# OfficeSign.net
KiCad netlist of a schematic drawn in EAGLE
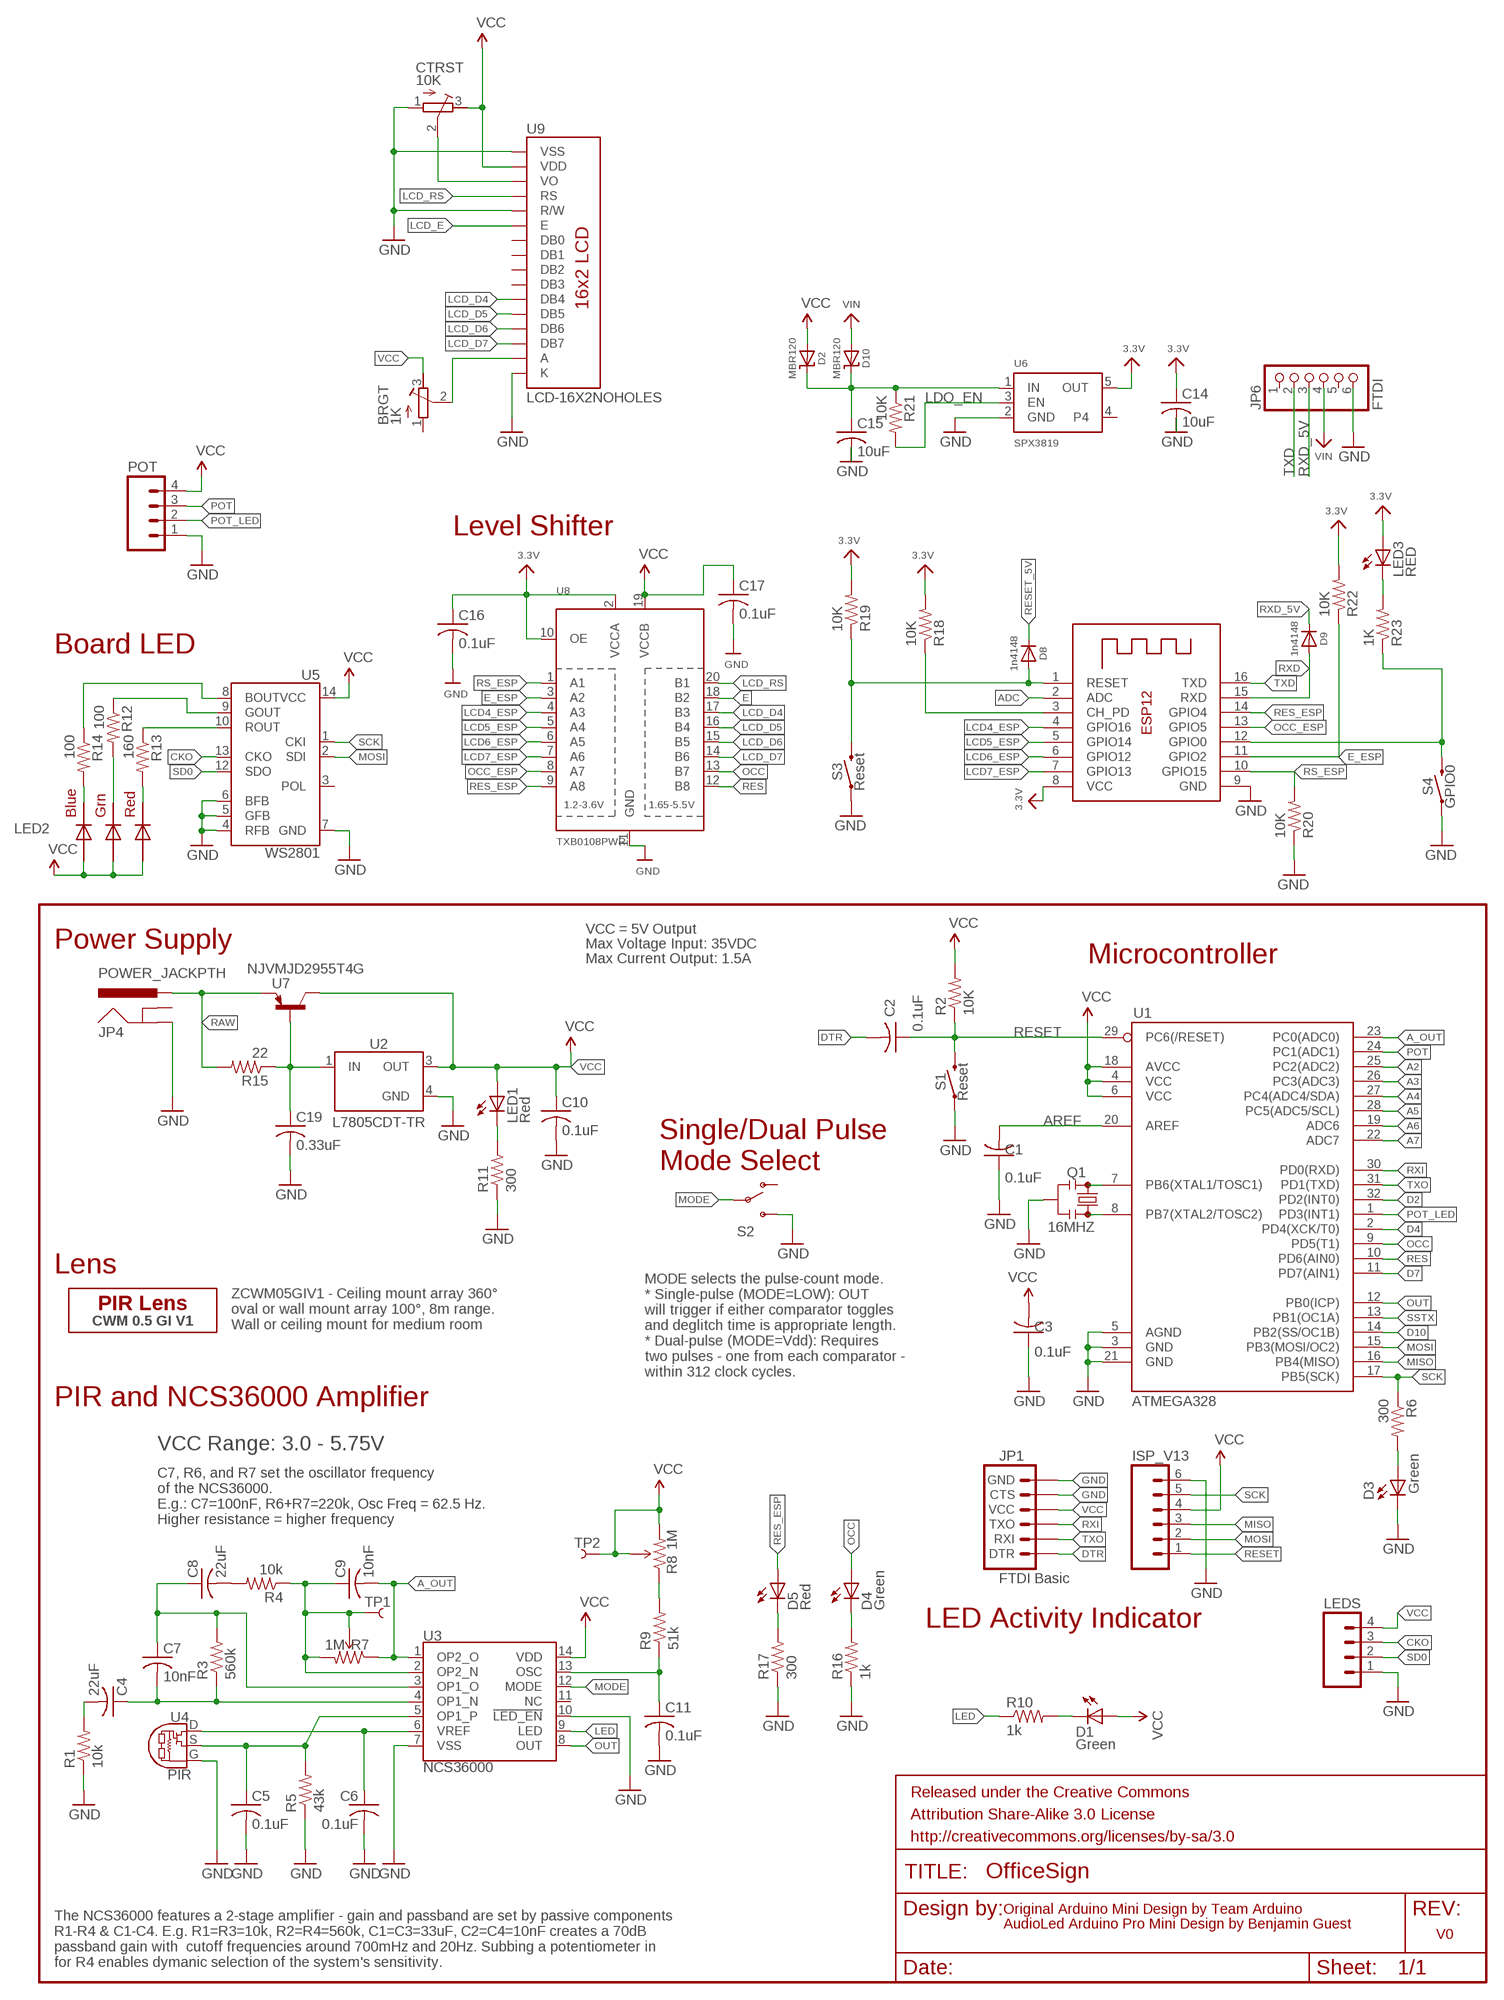
[diagram p0: schematic, sheet 1]

(export (version "E")
  (design (tool "Eeschema 10.0.6"))
  (components
    (comp (ref "BRGT")
      (value "1K")
      (footprint "eagle-import:RTRIM3296W")
      (libsource (lib "eagle-import") (part "R-TRIMM3296W"))
    )
    (comp (ref "C1")
      (value "0.1uF")
      (footprint "eagle-import:C0805")
      (libsource (lib "eagle-import") (part "C-USC0805"))
    )
    (comp (ref "C2")
      (value "0.1uF")
      (footprint "eagle-import:C0805")
      (libsource (lib "eagle-import") (part "C-USC0805"))
    )
    (comp (ref "C3")
      (value "0.1uF")
      (footprint "eagle-import:C0805")
      (libsource (lib "eagle-import") (part "C-USC0805"))
    )
    (comp (ref "C4")
      (value "22uF")
      (footprint "eagle-import:C0805")
      (libsource (lib "eagle-import") (part "C-USC0805"))
    )
    (comp (ref "C5")
      (value "0.1uF")
      (footprint "eagle-import:C0805")
      (libsource (lib "eagle-import") (part "C-USC0805"))
    )
    (comp (ref "C6")
      (value "0.1uF")
      (footprint "eagle-import:C0805")
      (libsource (lib "eagle-import") (part "C-USC0805"))
    )
    (comp (ref "C7")
      (value "10nF")
      (footprint "eagle-import:C0805")
      (libsource (lib "eagle-import") (part "C-USC0805"))
    )
    (comp (ref "C8")
      (value "22uF")
      (footprint "eagle-import:C0805")
      (libsource (lib "eagle-import") (part "C-USC0805"))
    )
    (comp (ref "C9")
      (value "10nF")
      (footprint "eagle-import:C0805")
      (libsource (lib "eagle-import") (part "C-USC0805"))
    )
    (comp (ref "C10")
      (value "0.1uF")
      (footprint "eagle-import:C0805")
      (libsource (lib "eagle-import") (part "C-USC0805"))
    )
    (comp (ref "C11")
      (value "0.1uF")
      (footprint "eagle-import:C0805")
      (libsource (lib "eagle-import") (part "C-USC0805"))
    )
    (comp (ref "C14")
      (value "10uF")
      (footprint "eagle-import:C0805")
      (libsource (lib "eagle-import") (part "C-USC0805"))
    )
    (comp (ref "C15")
      (value "10uF")
      (footprint "eagle-import:C0805")
      (libsource (lib "eagle-import") (part "C-USC0805"))
    )
    (comp (ref "C16")
      (value "0.1uF")
      (footprint "eagle-import:C0805")
      (libsource (lib "eagle-import") (part "rcl_334_C-USC0805"))
    )
    (comp (ref "C17")
      (value "0.1uF")
      (footprint "eagle-import:C0805")
      (libsource (lib "eagle-import") (part "rcl_334_C-USC0805"))
    )
    (comp (ref "C19")
      (value "0.33uF")
      (footprint "eagle-import:C0805")
      (libsource (lib "eagle-import") (part "C-USC0805"))
    )
    (comp (ref "CTRST")
      (value "10K")
      (footprint "eagle-import:RTRIM3296W")
      (libsource (lib "eagle-import") (part "R-TRIMM3296W"))
    )
    (comp (ref "D1")
      (value "Green")
      (footprint "eagle-import:CHIPLED_0805")
      (libsource (lib "eagle-import") (part "LEDCHIPLED_0805"))
    )
    (comp (ref "D2")
      (value "MBR120")
      (footprint "eagle-import:SOD-123")
      (libsource (lib "eagle-import") (part "DIODE-SCHOTTKYSOD-123"))
    )
    (comp (ref "D3")
      (value "Green")
      (footprint "eagle-import:CHIPLED_0805")
      (libsource (lib "eagle-import") (part "LEDCHIPLED_0805"))
    )
    (comp (ref "D4")
      (value "Green")
      (footprint "eagle-import:CHIPLED_0805")
      (libsource (lib "eagle-import") (part "LEDCHIPLED_0805"))
    )
    (comp (ref "D5")
      (value "Red")
      (footprint "eagle-import:CHIPLED_0805")
      (libsource (lib "eagle-import") (part "LEDCHIPLED_0805"))
    )
    (comp (ref "D8")
      (value "1n4148")
      (footprint "eagle-import:SOD-323")
      (libsource (lib "eagle-import") (part "DIODESOD-323"))
    )
    (comp (ref "D9")
      (value "1n4148")
      (footprint "eagle-import:SOD-323")
      (libsource (lib "eagle-import") (part "DIODESOD-323"))
    )
    (comp (ref "D10")
      (value "MBR120")
      (footprint "eagle-import:SOD-123")
      (libsource (lib "eagle-import") (part "DIODE-SCHOTTKYSOD-123"))
    )
    (comp (ref "FRAME1")
      (value "FRAME-LETTER")
      (footprint "eagle-import:CREATIVE_COMMONS")
      (libsource (lib "eagle-import") (part "FRAME-LETTER"))
    )
    (comp (ref "ISP_V13")
      (value "M06SIP")
      (footprint "eagle-import:1X06")
      (libsource (lib "eagle-import") (part "M06SIP"))
    )
    (comp (ref "JP1")
      (value "FTDI Basic")
      (footprint "eagle-import:1X06")
      (libsource (lib "eagle-import") (part "ARDUINO_SERIAL_PROGRAMPTH"))
    )
    (comp (ref "JP4")
      (value "POWER_JACKPTH")
      (footprint "eagle-import:POWER_JACK_PTH")
      (libsource (lib "eagle-import") (part "POWER_JACKPTH"))
    )
    (comp (ref "JP6")
      (value "FTDI")
      (footprint "eagle-import:1X06_ROUND_70")
      (libsource (lib "eagle-import") (part "HEADER-1X670MIL"))
    )
    (comp (ref "LED1")
      (value "Red")
      (footprint "eagle-import:CHIPLED_0805")
      (libsource (lib "eagle-import") (part "LEDCHIPLED_0805"))
    )
    (comp (ref "LED2")
      (value "RGBLED5050")
      (footprint "eagle-import:RGBLED5050")
      (libsource (lib "eagle-import") (part "RGBLED5050"))
    )
    (comp (ref "LED3")
      (value "RED")
      (footprint "eagle-import:CHIP-LED0805")
      (libsource (lib "eagle-import") (part "LEDCHIP-LED0805"))
    )
    (comp (ref "LEDS")
      (value "M04JST-PTH")
      (footprint "eagle-import:JST-4-PTH")
      (libsource (lib "eagle-import") (part "M04JST-PTH"))
    )
    (comp (ref "POT")
      (value "M04JST-PTH")
      (footprint "eagle-import:JST-4-PTH")
      (libsource (lib "eagle-import") (part "M04JST-PTH"))
    )
    (comp (ref "Q1")
      (value "16MHZ")
      (footprint "eagle-import:RESONATOR-SMD")
      (libsource (lib "eagle-import") (part "RESONATOR16MHZ"))
    )
    (comp (ref "R1")
      (value "10k")
      (footprint "eagle-import:M0805")
      (libsource (lib "eagle-import") (part "R-US_M0805"))
    )
    (comp (ref "R2")
      (value "10K")
      (footprint "eagle-import:M0805")
      (libsource (lib "eagle-import") (part "R-US_M0805"))
    )
    (comp (ref "R3")
      (value "560k")
      (footprint "eagle-import:M0805")
      (libsource (lib "eagle-import") (part "R-US_M0805"))
    )
    (comp (ref "R4")
      (value "10k")
      (footprint "eagle-import:M0805")
      (libsource (lib "eagle-import") (part "R-US_M0805"))
    )
    (comp (ref "R5")
      (value "43k")
      (footprint "eagle-import:M0805")
      (libsource (lib "eagle-import") (part "R-US_M0805"))
    )
    (comp (ref "R6")
      (value "300")
      (footprint "eagle-import:M0805")
      (libsource (lib "eagle-import") (part "R-US_M0805"))
    )
    (comp (ref "R7")
      (value "1M")
      (footprint "eagle-import:TRIMPOT-TC33X")
      (libsource (lib "eagle-import") (part "TRIMPOTTX33X-1M"))
    )
    (comp (ref "R8")
      (value "1M")
      (footprint "eagle-import:TRIMPOT-TC33X")
      (libsource (lib "eagle-import") (part "TRIMPOTTX33X-1M"))
    )
    (comp (ref "R9")
      (value "51k")
      (footprint "eagle-import:M0805")
      (libsource (lib "eagle-import") (part "R-US_M0805"))
    )
    (comp (ref "R10")
      (value "1k")
      (footprint "eagle-import:M0805")
      (libsource (lib "eagle-import") (part "R-US_M0805"))
    )
    (comp (ref "R11")
      (value "300")
      (footprint "eagle-import:M0805")
      (libsource (lib "eagle-import") (part "R-US_M0805"))
    )
    (comp (ref "R12")
      (value "100")
      (footprint "eagle-import:M0805")
      (libsource (lib "eagle-import") (part "R-US_M0805"))
    )
    (comp (ref "R13")
      (value "160")
      (footprint "eagle-import:M0805")
      (libsource (lib "eagle-import") (part "R-US_M0805"))
    )
    (comp (ref "R14")
      (value "100")
      (footprint "eagle-import:M0805")
      (libsource (lib "eagle-import") (part "R-US_M0805"))
    )
    (comp (ref "R15")
      (value "22")
      (footprint "eagle-import:M0805")
      (libsource (lib "eagle-import") (part "R-US_M0805"))
    )
    (comp (ref "R16")
      (value "1k")
      (footprint "eagle-import:M0805")
      (libsource (lib "eagle-import") (part "R-US_M0805"))
    )
    (comp (ref "R17")
      (value "300")
      (footprint "eagle-import:M0805")
      (libsource (lib "eagle-import") (part "R-US_M0805"))
    )
    (comp (ref "R18")
      (value "10K")
      (footprint "eagle-import:M0805")
      (libsource (lib "eagle-import") (part "R-US_M0805"))
    )
    (comp (ref "R19")
      (value "10K")
      (footprint "eagle-import:M0805")
      (libsource (lib "eagle-import") (part "R-US_M0805"))
    )
    (comp (ref "R20")
      (value "10K")
      (footprint "eagle-import:M0805")
      (libsource (lib "eagle-import") (part "R-US_M0805"))
    )
    (comp (ref "R21")
      (value "10K")
      (footprint "eagle-import:M0805")
      (libsource (lib "eagle-import") (part "R-US_M0805"))
    )
    (comp (ref "R22")
      (value "10K")
      (footprint "eagle-import:M0805")
      (libsource (lib "eagle-import") (part "R-US_M0805"))
    )
    (comp (ref "R23")
      (value "1K")
      (footprint "eagle-import:M0805")
      (libsource (lib "eagle-import") (part "R-US_M0805"))
    )
    (comp (ref "S1")
      (value "Reset")
      (footprint "eagle-import:TACTILE_SWITCH_SMD_5.2MM")
      (libsource (lib "eagle-import") (part "MOMENTARY-SWITCH-SPST-SMD-5.2-REDUNDANT"))
    )
    (comp (ref "S2")
      (value "SWITCH-SPDT-SMD-A")
      (footprint "eagle-import:SWITCH-SPST-SMD-A")
      (libsource (lib "eagle-import") (part "SWITCH-SPDT-SMD-A"))
    )
    (comp (ref "S3")
      (value "Reset")
      (footprint "eagle-import:TACTILE_SWITCH_SMD_5.2MM")
      (libsource (lib "eagle-import") (part "MOMENTARY-SWITCH-SPST-SMD-5.2-REDUNDANT"))
    )
    (comp (ref "S4")
      (value "GPIO0")
      (footprint "eagle-import:TACTILE_SWITCH_SMD_5.2MM")
      (libsource (lib "eagle-import") (part "MOMENTARY-SWITCH-SPST-SMD-5.2-REDUNDANT"))
    )
    (comp (ref "TP1")
      (value "TEST-POINT3X5")
      (footprint "eagle-import:PAD.03X.05")
      (libsource (lib "eagle-import") (part "TEST-POINT3X5"))
    )
    (comp (ref "TP2")
      (value "TEST-POINT3X5")
      (footprint "eagle-import:PAD.03X.05")
      (libsource (lib "eagle-import") (part "TEST-POINT3X5"))
    )
    (comp (ref "U$1")
      (value "CWM 0.5 GI V1")
      (footprint "eagle-import:LENS-CWM-0.5-GI-V1")
      (libsource (lib "eagle-import") (part "PIR-LENSCWM-0.5-GI-V1"))
    )
    (comp (ref "U1")
      (value "ATMEGA328")
      (footprint "eagle-import:TQFP32-08")
      (libsource (lib "eagle-import") (part "ATMEGA168"))
    )
    (comp (ref "U2")
      (value "L7805CDT-TR")
      (footprint "eagle-import:DPAK")
      (libsource (lib "eagle-import") (part "L7805CDT-TR"))
    )
    (comp (ref "U3")
      (value "NCS36000")
      (footprint "eagle-import:SO14")
      (libsource (lib "eagle-import") (part "NCS36000"))
    )
    (comp (ref "U4")
      (value "PIR")
      (footprint "eagle-import:PIR")
      (libsource (lib "eagle-import") (part "PIR"))
    )
    (comp (ref "U5")
      (value "WS2801")
      (footprint "eagle-import:SOP-14")
      (libsource (lib "eagle-import") (part "WS2801"))
    )
    (comp (ref "U6")
      (value "SPX3819")
      (footprint "eagle-import:SOT23-5")
      (libsource (lib "eagle-import") (part "VREG_SOT23-5"))
    )
    (comp (ref "U7")
      (value "NJVMJD2955T4G")
      (footprint "eagle-import:DPAK")
      (libsource (lib "eagle-import") (part "NJVMJD2955T4G"))
    )
    (comp (ref "U8")
      (value "TXB0108PWR")
      (footprint "eagle-import:TSSOP20")
      (libsource (lib "eagle-import") (part "TXB0108PWR"))
    )
    (comp (ref "U9")
      (value "LCD-16X2NOHOLES")
      (footprint "eagle-import:LCD-16X2_NOHOLES")
      (libsource (lib "eagle-import") (part "LCD-16X2NOHOLES"))
    )
    (comp (ref "X2")
      (value "ESP-12")
      (footprint "eagle-import:ESP-12")
      (libsource (lib "eagle-import") (part "ESP-12"))
    )
  )
  (nets
    (net (code "1") (name "/AREF") (class "Default")
      (node (ref "C1") (pin "2") (pinfunction "2_2") (pintype "passive"))
      (node (ref "U1") (pin "20") (pinfunction "AREF_20") (pintype "bidirectional"))
    )
    (net (code "2") (name "/LDO_EN") (class "Default")
      (node (ref "R21") (pin "2") (pinfunction "2_2") (pintype "passive"))
      (node (ref "U6") (pin "3") (pinfunction "EN_3") (pintype "input"))
    )
    (net (code "3") (name "3.3V") (class "Default")
      (node (ref "C14") (pin "1") (pinfunction "1_1") (pintype "passive"))
      (node (ref "C16") (pin "1") (pinfunction "1_1") (pintype "passive"))
      (node (ref "LED3") (pin "A") (pinfunction "A_A") (pintype "passive"))
      (node (ref "R18") (pin "2") (pinfunction "2_2") (pintype "passive"))
      (node (ref "R19") (pin "2") (pinfunction "2_2") (pintype "passive"))
      (node (ref "R22") (pin "2") (pinfunction "2_2") (pintype "passive"))
      (node (ref "U6") (pin "5") (pinfunction "OUT_5") (pintype "power_in"))
      (node (ref "U8") (pin "10") (pinfunction "OE_10") (pintype "bidirectional"))
      (node (ref "U8") (pin "2") (pinfunction "VCCA_2") (pintype "bidirectional"))
      (node (ref "X2") (pin "8") (pinfunction "VCC_8") (pintype "power_in"))
    )
    (net (code "4") (name "A2") (class "Default")
      (node (ref "U1") (pin "25") (pinfunction "PC2(ADC2)_25") (pintype "bidirectional"))
    )
    (net (code "5") (name "A3") (class "Default")
      (node (ref "U1") (pin "26") (pinfunction "PC3(ADC3)_26") (pintype "bidirectional"))
    )
    (net (code "6") (name "A4") (class "Default")
      (node (ref "U1") (pin "27") (pinfunction "PC4(ADC4/SDA)_27") (pintype "bidirectional"))
    )
    (net (code "7") (name "A5") (class "Default")
      (node (ref "U1") (pin "28") (pinfunction "PC5(ADC5/SCL)_28") (pintype "bidirectional"))
    )
    (net (code "8") (name "A6") (class "Default")
      (node (ref "U1") (pin "19") (pinfunction "ADC6_19") (pintype "bidirectional"))
    )
    (net (code "9") (name "A7") (class "Default")
      (node (ref "U1") (pin "22") (pinfunction "ADC7_22") (pintype "bidirectional"))
    )
    (net (code "10") (name "ADC") (class "Default")
      (node (ref "X2") (pin "2") (pinfunction "ADC_2") (pintype "passive"))
    )
    (net (code "11") (name "A_OUT") (class "Default")
      (node (ref "C9") (pin "2") (pinfunction "2_2") (pintype "passive"))
      (node (ref "R7") (pin "1") (pinfunction "CCW_1") (pintype "passive"))
      (node (ref "U1") (pin "23") (pinfunction "PC0(ADC0)_23") (pintype "bidirectional"))
      (node (ref "U3") (pin "1") (pinfunction "OP2_O_1") (pintype "bidirectional"))
    )
    (net (code "12") (name "CKO") (class "Default")
      (node (ref "LEDS") (pin "3") (pinfunction "3_3") (pintype "passive"))
      (node (ref "U5") (pin "13") (pinfunction "CKO_13") (pintype "bidirectional"))
    )
    (net (code "13") (name "D2") (class "Default")
      (node (ref "U1") (pin "32") (pinfunction "PD2(INT0)_32") (pintype "bidirectional"))
    )
    (net (code "14") (name "D4") (class "Default")
      (node (ref "U1") (pin "2") (pinfunction "PD4(XCK/T0)_2") (pintype "bidirectional"))
    )
    (net (code "15") (name "D7") (class "Default")
      (node (ref "U1") (pin "11") (pinfunction "PD7(AIN1)_11") (pintype "bidirectional"))
    )
    (net (code "16") (name "D10") (class "Default")
      (node (ref "U1") (pin "14") (pinfunction "PB2(SS/OC1B)_14") (pintype "bidirectional"))
    )
    (net (code "17") (name "DTR") (class "Default")
      (node (ref "C2") (pin "2") (pinfunction "2_2") (pintype "passive"))
      (node (ref "JP1") (pin "1") (pinfunction "DTR_1") (pintype "passive"))
    )
    (net (code "18") (name "E") (class "Default")
      (node (ref "U8") (pin "18") (pinfunction "B2_18") (pintype "bidirectional"))
    )
    (net (code "19") (name "E_ESP") (class "Default")
      (node (ref "R22") (pin "1") (pinfunction "1_1") (pintype "passive"))
      (node (ref "U8") (pin "3") (pinfunction "A2_3") (pintype "bidirectional"))
      (node (ref "X2") (pin "11") (pinfunction "GPIO2_11") (pintype "bidirectional"))
    )
    (net (code "20") (name "GND") (class "Default")
      (node (ref "C1") (pin "1") (pinfunction "1_1") (pintype "passive"))
      (node (ref "C10") (pin "2") (pinfunction "2_2") (pintype "passive"))
      (node (ref "C11") (pin "2") (pinfunction "2_2") (pintype "passive"))
      (node (ref "C14") (pin "2") (pinfunction "2_2") (pintype "passive"))
      (node (ref "C15") (pin "2") (pinfunction "2_2") (pintype "passive"))
      (node (ref "C16") (pin "2") (pinfunction "2_2") (pintype "passive"))
      (node (ref "C17") (pin "2") (pinfunction "2_2") (pintype "passive"))
      (node (ref "C19") (pin "2") (pinfunction "2_2") (pintype "passive"))
      (node (ref "C3") (pin "1") (pinfunction "1_1") (pintype "passive"))
      (node (ref "C5") (pin "2") (pinfunction "2_2") (pintype "passive"))
      (node (ref "C6") (pin "2") (pinfunction "2_2") (pintype "passive"))
      (node (ref "CTRST") (pin "1") (pinfunction "A_1") (pintype "passive"))
      (node (ref "D3") (pin "C") (pinfunction "C_C") (pintype "passive"))
      (node (ref "ISP_V13") (pin "6") (pinfunction "6_6") (pintype "passive"))
      (node (ref "JP1") (pin "5") (pinfunction "CTS_5") (pintype "passive"))
      (node (ref "JP1") (pin "6") (pinfunction "GND_6") (pintype "passive"))
      (node (ref "JP4") (pin "GND") (pinfunction "GND_GND") (pintype "bidirectional"))
      (node (ref "JP6") (pin "6") (pinfunction "6_6") (pintype "passive"))
      (node (ref "LEDS") (pin "1") (pinfunction "1_1") (pintype "passive"))
      (node (ref "POT") (pin "1") (pinfunction "1_1") (pintype "passive"))
      (node (ref "Q1") (pin "2") (pinfunction "2_2") (pintype "passive"))
      (node (ref "R1") (pin "1") (pinfunction "1_1") (pintype "passive"))
      (node (ref "R11") (pin "1") (pinfunction "1_1") (pintype "passive"))
      (node (ref "R16") (pin "1") (pinfunction "1_1") (pintype "passive"))
      (node (ref "R17") (pin "1") (pinfunction "1_1") (pintype "passive"))
      (node (ref "R20") (pin "1") (pinfunction "1_1") (pintype "passive"))
      (node (ref "R5") (pin "1") (pinfunction "1_1") (pintype "passive"))
      (node (ref "S1") (pin "1") (pinfunction "1_1") (pintype "passive"))
      (node (ref "S1") (pin "2") (pinfunction "1_2") (pintype "passive"))
      (node (ref "S2") (pin "3") (pinfunction "S_3") (pintype "passive"))
      (node (ref "S3") (pin "1") (pinfunction "1_1") (pintype "passive"))
      (node (ref "S3") (pin "2") (pinfunction "1_2") (pintype "passive"))
      (node (ref "S4") (pin "1") (pinfunction "1_1") (pintype "passive"))
      (node (ref "S4") (pin "2") (pinfunction "1_2") (pintype "passive"))
      (node (ref "U1") (pin "21") (pinfunction "GND_21") (pintype "bidirectional"))
      (node (ref "U1") (pin "3") (pinfunction "GND_3") (pintype "bidirectional"))
      (node (ref "U1") (pin "5") (pinfunction "AGND_5") (pintype "bidirectional"))
      (node (ref "U2") (pin "4") (pinfunction "GND_4") (pintype "power_in"))
      (node (ref "U3") (pin "10") (pinfunction "~{LED_EN}_10") (pintype "bidirectional"))
      (node (ref "U3") (pin "7") (pinfunction "VSS_7") (pintype "bidirectional"))
      (node (ref "U4") (pin "G") (pinfunction "G_G") (pintype "bidirectional"))
      (node (ref "U5") (pin "4") (pinfunction "RFB_4") (pintype "bidirectional"))
      (node (ref "U5") (pin "5") (pinfunction "GFB_5") (pintype "bidirectional"))
      (node (ref "U5") (pin "6") (pinfunction "BFB_6") (pintype "bidirectional"))
      (node (ref "U5") (pin "7") (pinfunction "GND_7") (pintype "bidirectional"))
      (node (ref "U6") (pin "2") (pinfunction "GND_2") (pintype "power_in"))
      (node (ref "U8") (pin "11") (pinfunction "GND_11") (pintype "bidirectional"))
      (node (ref "U9") (pin "1") (pinfunction "VSS_1") (pintype "power_in"))
      (node (ref "U9") (pin "16") (pinfunction "K_16") (pintype "power_in"))
      (node (ref "U9") (pin "5") (pinfunction "R/W_5") (pintype "input"))
      (node (ref "X2") (pin "9") (pinfunction "GND_9") (pintype "power_in"))
    )
    (net (code "21") (name "LCD4_ESP") (class "Default")
      (node (ref "U8") (pin "4") (pinfunction "A3_4") (pintype "bidirectional"))
      (node (ref "X2") (pin "4") (pinfunction "GPIO16_4") (pintype "bidirectional"))
    )
    (net (code "22") (name "LCD5_ESP") (class "Default")
      (node (ref "U8") (pin "5") (pinfunction "A4_5") (pintype "bidirectional"))
      (node (ref "X2") (pin "5") (pinfunction "GPIO14_5") (pintype "bidirectional"))
    )
    (net (code "23") (name "LCD6_ESP") (class "Default")
      (node (ref "U8") (pin "6") (pinfunction "A5_6") (pintype "bidirectional"))
      (node (ref "X2") (pin "6") (pinfunction "GPIO12_6") (pintype "bidirectional"))
    )
    (net (code "24") (name "LCD7_ESP") (class "Default")
      (node (ref "U8") (pin "7") (pinfunction "A6_7") (pintype "bidirectional"))
      (node (ref "X2") (pin "7") (pinfunction "GPIO13_7") (pintype "bidirectional"))
    )
    (net (code "25") (name "LCD_D4") (class "Default")
      (node (ref "U8") (pin "17") (pinfunction "B3_17") (pintype "bidirectional"))
      (node (ref "U9") (pin "11") (pinfunction "DB4_11") (pintype "bidirectional"))
    )
    (net (code "26") (name "LCD_D5") (class "Default")
      (node (ref "U8") (pin "16") (pinfunction "B4_16") (pintype "bidirectional"))
      (node (ref "U9") (pin "12") (pinfunction "DB5_12") (pintype "bidirectional"))
    )
    (net (code "27") (name "LCD_D6") (class "Default")
      (node (ref "U8") (pin "15") (pinfunction "B5_15") (pintype "bidirectional"))
      (node (ref "U9") (pin "13") (pinfunction "DB6_13") (pintype "bidirectional"))
    )
    (net (code "28") (name "LCD_D7") (class "Default")
      (node (ref "U8") (pin "14") (pinfunction "B6_14") (pintype "bidirectional"))
      (node (ref "U9") (pin "14") (pinfunction "DB7_14") (pintype "bidirectional"))
    )
    (net (code "29") (name "LCD_E") (class "Default")
      (node (ref "U9") (pin "6") (pinfunction "E_6") (pintype "input"))
    )
    (net (code "30") (name "LCD_RS") (class "Default")
      (node (ref "U8") (pin "20") (pinfunction "B1_20") (pintype "bidirectional"))
      (node (ref "U9") (pin "4") (pinfunction "RS_4") (pintype "input"))
    )
    (net (code "31") (name "LED") (class "Default")
      (node (ref "R10") (pin "1") (pinfunction "1_1") (pintype "passive"))
      (node (ref "U3") (pin "9") (pinfunction "LED_9") (pintype "bidirectional"))
    )
    (net (code "32") (name "MISO") (class "Default")
      (node (ref "ISP_V13") (pin "3") (pinfunction "3_3") (pintype "passive"))
      (node (ref "U1") (pin "16") (pinfunction "PB4(MISO)_16") (pintype "bidirectional"))
    )
    (net (code "33") (name "MODE") (class "Default")
      (node (ref "S2") (pin "2") (pinfunction "P_2") (pintype "passive"))
      (node (ref "U3") (pin "12") (pinfunction "MODE_12") (pintype "bidirectional"))
    )
    (net (code "34") (name "MOSI") (class "Default")
      (node (ref "ISP_V13") (pin "2") (pinfunction "2_2") (pintype "passive"))
      (node (ref "U1") (pin "15") (pinfunction "PB3(MOSI/OC2)_15") (pintype "bidirectional"))
      (node (ref "U5") (pin "2") (pinfunction "SDI_2") (pintype "bidirectional"))
    )
    (net (code "35") (name "Net-(BRGT-S)") (class "Default")
      (node (ref "BRGT") (pin "2") (pinfunction "S_2") (pintype "passive"))
      (node (ref "U9") (pin "15") (pinfunction "A_15") (pintype "power_in"))
    )
    (net (code "36") (name "Net-(C4-Pad2)") (class "Default")
      (node (ref "C4") (pin "2") (pinfunction "2_2") (pintype "passive"))
      (node (ref "R1") (pin "2") (pinfunction "2_2") (pintype "passive"))
    )
    (net (code "37") (name "Net-(C8-Pad2)") (class "Default")
      (node (ref "C8") (pin "2") (pinfunction "2_2") (pintype "passive"))
      (node (ref "R4") (pin "2") (pinfunction "2_2") (pintype "passive"))
    )
    (net (code "38") (name "Net-(CTRST-S)") (class "Default")
      (node (ref "CTRST") (pin "2") (pinfunction "S_2") (pintype "passive"))
      (node (ref "U9") (pin "3") (pinfunction "VO_3") (pintype "bidirectional"))
    )
    (net (code "39") (name "Net-(D1-PadC)") (class "Default")
      (node (ref "D1") (pin "C") (pinfunction "C_C") (pintype "passive"))
      (node (ref "R10") (pin "2") (pinfunction "2_2") (pintype "passive"))
    )
    (net (code "40") (name "Net-(D3-PadA)") (class "Default")
      (node (ref "D3") (pin "A") (pinfunction "A_A") (pintype "passive"))
      (node (ref "R6") (pin "2") (pinfunction "2_2") (pintype "passive"))
    )
    (net (code "41") (name "Net-(D4-PadC)") (class "Default")
      (node (ref "D4") (pin "C") (pinfunction "C_C") (pintype "passive"))
      (node (ref "R16") (pin "2") (pinfunction "2_2") (pintype "passive"))
    )
    (net (code "42") (name "Net-(D5-PadC)") (class "Default")
      (node (ref "D5") (pin "C") (pinfunction "C_C") (pintype "passive"))
      (node (ref "R17") (pin "2") (pinfunction "2_2") (pintype "passive"))
    )
    (net (code "43") (name "Net-(LED1-PadC)") (class "Default")
      (node (ref "LED1") (pin "C") (pinfunction "C_C") (pintype "passive"))
      (node (ref "R11") (pin "2") (pinfunction "2_2") (pintype "passive"))
    )
    (net (code "44") (name "Net-(LED2-BLUE_C)") (class "Default")
      (node (ref "LED2") (pin "4") (pinfunction "BLUE_C_4") (pintype "bidirectional"))
      (node (ref "R14") (pin "2") (pinfunction "2_2") (pintype "passive"))
    )
    (net (code "45") (name "Net-(LED2-GREEN_C)") (class "Default")
      (node (ref "LED2") (pin "6") (pinfunction "GREEN_C_6") (pintype "bidirectional"))
      (node (ref "R12") (pin "2") (pinfunction "2_2") (pintype "passive"))
    )
    (net (code "46") (name "Net-(LED2-RED_C)") (class "Default")
      (node (ref "LED2") (pin "5") (pinfunction "RED_C_5") (pintype "bidirectional"))
      (node (ref "R13") (pin "2") (pinfunction "2_2") (pintype "passive"))
    )
    (net (code "47") (name "Net-(LED3-PadC)") (class "Default")
      (node (ref "LED3") (pin "C") (pinfunction "C_C") (pintype "passive"))
      (node (ref "R23") (pin "2") (pinfunction "2_2") (pintype "passive"))
    )
    (net (code "48") (name "Net-(R7-CW)") (class "Default")
      (node (ref "C9") (pin "1") (pinfunction "1_1") (pintype "passive"))
      (node (ref "R4") (pin "1") (pinfunction "1_1") (pintype "passive"))
      (node (ref "R7") (pin "2") (pinfunction "WIPER_2") (pintype "passive"))
      (node (ref "R7") (pin "3") (pinfunction "CW_3") (pintype "passive"))
      (node (ref "TP1") (pin "P$1") (pinfunction "1_P$1") (pintype "bidirectional"))
      (node (ref "U3") (pin "2") (pinfunction "OP2_N_2") (pintype "bidirectional"))
    )
    (net (code "49") (name "Net-(R8-CCW)") (class "Default")
      (node (ref "R8") (pin "1") (pinfunction "CCW_1") (pintype "passive"))
      (node (ref "R9") (pin "2") (pinfunction "2_2") (pintype "passive"))
    )
    (net (code "50") (name "Net-(U1-PB6(XTAL1{slash}TOSC1))") (class "Default")
      (node (ref "Q1") (pin "1") (pinfunction "1_1") (pintype "passive"))
      (node (ref "U1") (pin "7") (pinfunction "PB6(XTAL1/TOSC1)_7") (pintype "bidirectional"))
    )
    (net (code "51") (name "Net-(U1-PB7(XTAL2{slash}TOSC2))") (class "Default")
      (node (ref "Q1") (pin "3") (pinfunction "3_3") (pintype "passive"))
      (node (ref "U1") (pin "8") (pinfunction "PB7(XTAL2/TOSC2)_8") (pintype "bidirectional"))
    )
    (net (code "52") (name "Net-(U2-IN)") (class "Default")
      (node (ref "C19") (pin "1") (pinfunction "1_1") (pintype "passive"))
      (node (ref "R15") (pin "1") (pinfunction "1_1") (pintype "passive"))
      (node (ref "U2") (pin "1") (pinfunction "IN_1") (pintype "power_in"))
      (node (ref "U7") (pin "1") (pinfunction "B_1") (pintype "passive"))
    )
    (net (code "53") (name "Net-(U3-OP1_N)") (class "Default")
      (node (ref "C4") (pin "1") (pinfunction "1_1") (pintype "passive"))
      (node (ref "C7") (pin "2") (pinfunction "2_2") (pintype "passive"))
      (node (ref "R3") (pin "1") (pinfunction "1_1") (pintype "passive"))
      (node (ref "U3") (pin "4") (pinfunction "OP1_N_4") (pintype "bidirectional"))
    )
    (net (code "54") (name "Net-(U3-OP1_O)") (class "Default")
      (node (ref "C7") (pin "1") (pinfunction "1_1") (pintype "passive"))
      (node (ref "C8") (pin "1") (pinfunction "1_1") (pintype "passive"))
      (node (ref "R3") (pin "2") (pinfunction "2_2") (pintype "passive"))
      (node (ref "U3") (pin "3") (pinfunction "OP1_O_3") (pintype "bidirectional"))
    )
    (net (code "55") (name "Net-(U3-OP1_P)") (class "Default")
      (node (ref "C5") (pin "1") (pinfunction "1_1") (pintype "passive"))
      (node (ref "R5") (pin "2") (pinfunction "2_2") (pintype "passive"))
      (node (ref "U3") (pin "5") (pinfunction "OP1_P_5") (pintype "bidirectional"))
      (node (ref "U4") (pin "S") (pinfunction "S_S") (pintype "bidirectional"))
    )
    (net (code "56") (name "Net-(U3-OSC)") (class "Default")
      (node (ref "C11") (pin "1") (pinfunction "1_1") (pintype "passive"))
      (node (ref "R9") (pin "1") (pinfunction "1_1") (pintype "passive"))
      (node (ref "U3") (pin "13") (pinfunction "OSC_13") (pintype "bidirectional"))
    )
    (net (code "57") (name "Net-(U3-VREF)") (class "Default")
      (node (ref "C6") (pin "1") (pinfunction "1_1") (pintype "passive"))
      (node (ref "U3") (pin "6") (pinfunction "VREF_6") (pintype "bidirectional"))
      (node (ref "U4") (pin "D") (pinfunction "D_D") (pintype "bidirectional"))
    )
    (net (code "58") (name "Net-(U5-BOUT)") (class "Default")
      (node (ref "R14") (pin "1") (pinfunction "1_1") (pintype "passive"))
      (node (ref "U5") (pin "8") (pinfunction "BOUT_8") (pintype "bidirectional"))
    )
    (net (code "59") (name "Net-(U5-GOUT)") (class "Default")
      (node (ref "R12") (pin "1") (pinfunction "1_1") (pintype "passive"))
      (node (ref "U5") (pin "9") (pinfunction "GOUT_9") (pintype "bidirectional"))
    )
    (net (code "60") (name "Net-(U5-ROUT)") (class "Default")
      (node (ref "R13") (pin "1") (pinfunction "1_1") (pintype "passive"))
      (node (ref "U5") (pin "10") (pinfunction "ROUT_10") (pintype "bidirectional"))
    )
    (net (code "61") (name "Net-(U6-IN)") (class "Default")
      (node (ref "C15") (pin "1") (pinfunction "1_1") (pintype "passive"))
      (node (ref "D10") (pin "C") (pinfunction "C_C") (pintype "passive"))
      (node (ref "D2") (pin "C") (pinfunction "C_C") (pintype "passive"))
      (node (ref "R21") (pin "1") (pinfunction "1_1") (pintype "passive"))
      (node (ref "U6") (pin "1") (pinfunction "IN_1") (pintype "power_in"))
    )
    (net (code "62") (name "Net-(X2-CH_PD)") (class "Default")
      (node (ref "R18") (pin "1") (pinfunction "1_1") (pintype "passive"))
      (node (ref "X2") (pin "3") (pinfunction "CH_PD_3") (pintype "input"))
    )
    (net (code "63") (name "Net-(X2-GPIO0)") (class "Default")
      (node (ref "R23") (pin "1") (pinfunction "1_1") (pintype "passive"))
      (node (ref "S4") (pin "3") (pinfunction "2_3") (pintype "passive"))
      (node (ref "S4") (pin "4") (pinfunction "2_4") (pintype "passive"))
      (node (ref "X2") (pin "12") (pinfunction "GPIO0_12") (pintype "bidirectional"))
    )
    (net (code "64") (name "Net-(X2-RESET)") (class "Default")
      (node (ref "D8") (pin "A") (pinfunction "A_A") (pintype "passive"))
      (node (ref "R19") (pin "1") (pinfunction "1_1") (pintype "passive"))
      (node (ref "S3") (pin "3") (pinfunction "2_3") (pintype "passive"))
      (node (ref "S3") (pin "4") (pinfunction "2_4") (pintype "passive"))
      (node (ref "X2") (pin "1") (pinfunction "RESET_1") (pintype "input"))
    )
    (net (code "65") (name "OCC") (class "Default")
      (node (ref "D4") (pin "A") (pinfunction "A_A") (pintype "passive"))
      (node (ref "U1") (pin "9") (pinfunction "PD5(T1)_9") (pintype "bidirectional"))
      (node (ref "U8") (pin "13") (pinfunction "B7_13") (pintype "bidirectional"))
    )
    (net (code "66") (name "OCC_ESP") (class "Default")
      (node (ref "U8") (pin "8") (pinfunction "A7_8") (pintype "bidirectional"))
      (node (ref "X2") (pin "13") (pinfunction "GPIO5_13") (pintype "bidirectional"))
    )
    (net (code "67") (name "OUT") (class "Default")
      (node (ref "U1") (pin "12") (pinfunction "PB0(ICP)_12") (pintype "bidirectional"))
      (node (ref "U3") (pin "8") (pinfunction "OUT_8") (pintype "bidirectional"))
    )
    (net (code "68") (name "POT") (class "Default")
      (node (ref "POT") (pin "3") (pinfunction "3_3") (pintype "passive"))
      (node (ref "U1") (pin "24") (pinfunction "PC1(ADC1)_24") (pintype "bidirectional"))
    )
    (net (code "69") (name "POT_LED") (class "Default")
      (node (ref "POT") (pin "2") (pinfunction "2_2") (pintype "passive"))
      (node (ref "U1") (pin "1") (pinfunction "PD3(INT1)_1") (pintype "bidirectional"))
    )
    (net (code "70") (name "RAW") (class "Default")
      (node (ref "JP4") (pin "PWR") (pinfunction "PWR_PWR") (pintype "bidirectional"))
      (node (ref "R15") (pin "2") (pinfunction "2_2") (pintype "passive"))
      (node (ref "U7") (pin "3") (pinfunction "E_3") (pintype "passive"))
    )
    (net (code "71") (name "RES") (class "Default")
      (node (ref "U1") (pin "10") (pinfunction "PD6(AIN0)_10") (pintype "bidirectional"))
      (node (ref "U8") (pin "12") (pinfunction "B8_12") (pintype "bidirectional"))
    )
    (net (code "72") (name "RESET") (class "Default")
      (node (ref "C2") (pin "1") (pinfunction "1_1") (pintype "passive"))
      (node (ref "ISP_V13") (pin "1") (pinfunction "1_1") (pintype "passive"))
      (node (ref "R2") (pin "1") (pinfunction "1_1") (pintype "passive"))
      (node (ref "S1") (pin "3") (pinfunction "2_3") (pintype "passive"))
      (node (ref "S1") (pin "4") (pinfunction "2_4") (pintype "passive"))
      (node (ref "U1") (pin "29") (pinfunction "PC6(/RESET)_29") (pintype "bidirectional"))
    )
    (net (code "73") (name "RESET_5V") (class "Default")
      (node (ref "D8") (pin "C") (pinfunction "C_C") (pintype "passive"))
    )
    (net (code "74") (name "RES_ESP") (class "Default")
      (node (ref "D5") (pin "A") (pinfunction "A_A") (pintype "passive"))
      (node (ref "U8") (pin "9") (pinfunction "A8_9") (pintype "bidirectional"))
      (node (ref "X2") (pin "14") (pinfunction "GPIO4_14") (pintype "bidirectional"))
    )
    (net (code "75") (name "RS_ESP") (class "Default")
      (node (ref "R20") (pin "2") (pinfunction "2_2") (pintype "passive"))
      (node (ref "U8") (pin "1") (pinfunction "A1_1") (pintype "bidirectional"))
      (node (ref "X2") (pin "10") (pinfunction "GPIO15_10") (pintype "bidirectional"))
    )
    (net (code "76") (name "RXD") (class "Default")
      (node (ref "D9") (pin "A") (pinfunction "A_A") (pintype "passive"))
      (node (ref "X2") (pin "15") (pinfunction "RXD_15") (pintype "input"))
    )
    (net (code "77") (name "RXD_5V") (class "Default")
      (node (ref "D9") (pin "C") (pinfunction "C_C") (pintype "passive"))
      (node (ref "JP6") (pin "3") (pinfunction "3_3") (pintype "passive"))
    )
    (net (code "78") (name "RXI") (class "Default")
      (node (ref "JP1") (pin "3") (pinfunction "TXO_3") (pintype "passive"))
      (node (ref "U1") (pin "30") (pinfunction "PD0(RXD)_30") (pintype "bidirectional"))
    )
    (net (code "79") (name "SCK") (class "Default")
      (node (ref "ISP_V13") (pin "5") (pinfunction "5_5") (pintype "passive"))
      (node (ref "R6") (pin "1") (pinfunction "1_1") (pintype "passive"))
      (node (ref "U1") (pin "17") (pinfunction "PB5(SCK)_17") (pintype "bidirectional"))
      (node (ref "U5") (pin "1") (pinfunction "CKI_1") (pintype "bidirectional"))
    )
    (net (code "80") (name "SD0") (class "Default")
      (node (ref "LEDS") (pin "2") (pinfunction "2_2") (pintype "passive"))
      (node (ref "U5") (pin "12") (pinfunction "SDO_12") (pintype "bidirectional"))
    )
    (net (code "81") (name "SSTX") (class "Default")
      (node (ref "U1") (pin "13") (pinfunction "PB1(OC1A)_13") (pintype "bidirectional"))
    )
    (net (code "82") (name "TXD") (class "Default")
      (node (ref "JP6") (pin "2") (pinfunction "2_2") (pintype "passive"))
      (node (ref "X2") (pin "16") (pinfunction "TXD_16") (pintype "output"))
    )
    (net (code "83") (name "TXO") (class "Default")
      (node (ref "JP1") (pin "2") (pinfunction "RXI_2") (pintype "passive"))
      (node (ref "U1") (pin "31") (pinfunction "PD1(TXD)_31") (pintype "bidirectional"))
    )
    (net (code "84") (name "VCC") (class "Default")
      (node (ref "BRGT") (pin "3") (pinfunction "E_3") (pintype "passive"))
      (node (ref "C10") (pin "1") (pinfunction "1_1") (pintype "passive"))
      (node (ref "C17") (pin "1") (pinfunction "1_1") (pintype "passive"))
      (node (ref "C3") (pin "2") (pinfunction "2_2") (pintype "passive"))
      (node (ref "CTRST") (pin "3") (pinfunction "E_3") (pintype "passive"))
      (node (ref "D1") (pin "A") (pinfunction "A_A") (pintype "passive"))
      (node (ref "D2") (pin "A") (pinfunction "A_A") (pintype "passive"))
      (node (ref "ISP_V13") (pin "4") (pinfunction "4_4") (pintype "passive"))
      (node (ref "JP1") (pin "4") (pinfunction "VCC_4") (pintype "passive"))
      (node (ref "LED1") (pin "A") (pinfunction "A_A") (pintype "passive"))
      (node (ref "LED2") (pin "1") (pinfunction "GREEN_A_1") (pintype "bidirectional"))
      (node (ref "LED2") (pin "2") (pinfunction "RED_A_2") (pintype "bidirectional"))
      (node (ref "LED2") (pin "3") (pinfunction "BLUE_A_3") (pintype "bidirectional"))
      (node (ref "LEDS") (pin "4") (pinfunction "4_4") (pintype "passive"))
      (node (ref "POT") (pin "4") (pinfunction "4_4") (pintype "passive"))
      (node (ref "R2") (pin "2") (pinfunction "2_2") (pintype "passive"))
      (node (ref "R8") (pin "2") (pinfunction "WIPER_2") (pintype "passive"))
      (node (ref "R8") (pin "3") (pinfunction "CW_3") (pintype "passive"))
      (node (ref "TP2") (pin "P$1") (pinfunction "1_P$1") (pintype "bidirectional"))
      (node (ref "U1") (pin "18") (pinfunction "AVCC_18") (pintype "bidirectional"))
      (node (ref "U1") (pin "4") (pinfunction "VCC_4") (pintype "bidirectional"))
      (node (ref "U1") (pin "6") (pinfunction "VCC_6") (pintype "bidirectional"))
      (node (ref "U2") (pin "3") (pinfunction "OUT_3") (pintype "power_in"))
      (node (ref "U3") (pin "14") (pinfunction "VDD_14") (pintype "bidirectional"))
      (node (ref "U5") (pin "14") (pinfunction "VCC_14") (pintype "bidirectional"))
      (node (ref "U7") (pin "4") (pinfunction "C_4") (pintype "passive"))
      (node (ref "U8") (pin "19") (pinfunction "VCCB_19") (pintype "bidirectional"))
      (node (ref "U9") (pin "2") (pinfunction "VDD_2") (pintype "power_in"))
    )
    (net (code "85") (name "VIN") (class "Default")
      (node (ref "D10") (pin "A") (pinfunction "A_A") (pintype "passive"))
      (node (ref "JP6") (pin "4") (pinfunction "4_4") (pintype "passive"))
    )
    (net (code "86") (name "unconnected-(BRGT-A-Pad1)") (class "Default")
      (node (ref "BRGT") (pin "1") (pinfunction "A_1") (pintype "passive"))
    )
    (net (code "87") (name "unconnected-(JP4-PadGNDBREAK)") (class "Default")
      (node (ref "JP4") (pin "GNDBREAK") (pinfunction "GNDBREAK_GNDBREAK") (pintype "bidirectional"))
    )
    (net (code "88") (name "unconnected-(JP6-Pad1)") (class "Default")
      (node (ref "JP6") (pin "1") (pinfunction "1_1") (pintype "passive"))
    )
    (net (code "89") (name "unconnected-(JP6-Pad5)") (class "Default")
      (node (ref "JP6") (pin "5") (pinfunction "5_5") (pintype "passive"))
    )
    (net (code "90") (name "unconnected-(S2-O-Pad1)") (class "Default")
      (node (ref "S2") (pin "1") (pinfunction "O_1") (pintype "passive"))
    )
    (net (code "91") (name "unconnected-(U3-NC-Pad11)") (class "Default")
      (node (ref "U3") (pin "11") (pinfunction "NC_11") (pintype "bidirectional"))
    )
    (net (code "92") (name "unconnected-(U5-POL-Pad3)") (class "Default")
      (node (ref "U5") (pin "3") (pinfunction "POL_3") (pintype "bidirectional"))
    )
    (net (code "93") (name "unconnected-(U6-P4-Pad4)") (class "Default")
      (node (ref "U6") (pin "4") (pinfunction "P4_4") (pintype "bidirectional"))
    )
    (net (code "94") (name "unconnected-(U9-DB0-Pad7)") (class "Default")
      (node (ref "U9") (pin "7") (pinfunction "DB0_7") (pintype "bidirectional"))
    )
    (net (code "95") (name "unconnected-(U9-DB1-Pad8)") (class "Default")
      (node (ref "U9") (pin "8") (pinfunction "DB1_8") (pintype "bidirectional"))
    )
    (net (code "96") (name "unconnected-(U9-DB2-Pad9)") (class "Default")
      (node (ref "U9") (pin "9") (pinfunction "DB2_9") (pintype "bidirectional"))
    )
    (net (code "97") (name "unconnected-(U9-DB3-Pad10)") (class "Default")
      (node (ref "U9") (pin "10") (pinfunction "DB3_10") (pintype "bidirectional"))
    )
  )
)
